# NixieSocket.net
KiCad netlist of a schematic drawn in Altium Designer
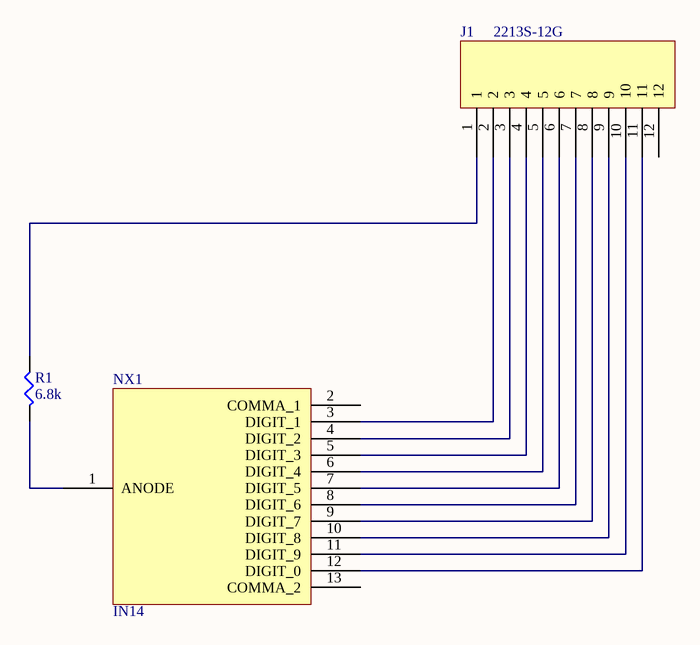
[diagram p0: NixieSocket.SchDoc]

(export (version "E")
  (design (tool "Eeschema 10.0.6"))
  (components
    (comp (ref "J1")
      (value "2213S-12G")
      (footprint "Header 2.54mm 6x2 - Male")
      (libsource (lib "Connectors") (part "2213S-12G"))
    )
    (comp (ref "NX1")
      (value "IN14")
      (footprint "IN-14 Nixie Tube")
      (description "IN-14 Nixie Tube")
      (libsource (lib "IN14") (part "IN14"))
    )
    (comp (ref "R1")
      (value "6.8k")
      (footprint "SMD-0805-RES")
      (description "RES SMD 6.8K OHM 1% 1/2W 0805")
      (fields
        (field (name "PART NUMBER") "ERJ-P6WF6801V")
        (field (name "DIGI-KEY PART NUMBER") "P16895CT-ND")
      )
      (libsource (lib "Panasonic_ERJ_0805") (part "ERJ-P6WF6801V"))
    )
  )
  (nets
    (net (code "1") (name "Net-(J1-Pad1)") (class "Default")
      (node (ref "J1") (pin "1") (pinfunction "1_1") (pintype "passive"))
      (node (ref "R1") (pin "1") (pinfunction "1_1") (pintype "passive"))
    )
    (net (code "2") (name "Net-(NX1-ANODE)") (class "Default")
      (node (ref "NX1") (pin "1") (pinfunction "ANODE_1") (pintype "passive"))
      (node (ref "R1") (pin "2") (pinfunction "2_2") (pintype "passive"))
    )
    (net (code "3") (name "Net-(NX1-DIGIT_0)") (class "Default")
      (node (ref "J1") (pin "11") (pinfunction "11_11") (pintype "passive"))
      (node (ref "NX1") (pin "12") (pinfunction "DIGIT_0_12") (pintype "passive"))
    )
    (net (code "4") (name "Net-(NX1-DIGIT_1)") (class "Default")
      (node (ref "J1") (pin "2") (pinfunction "2_2") (pintype "passive"))
      (node (ref "NX1") (pin "3") (pinfunction "DIGIT_1_3") (pintype "passive"))
    )
    (net (code "5") (name "Net-(NX1-DIGIT_2)") (class "Default")
      (node (ref "J1") (pin "3") (pinfunction "3_3") (pintype "passive"))
      (node (ref "NX1") (pin "4") (pinfunction "DIGIT_2_4") (pintype "passive"))
    )
    (net (code "6") (name "Net-(NX1-DIGIT_3)") (class "Default")
      (node (ref "J1") (pin "4") (pinfunction "4_4") (pintype "passive"))
      (node (ref "NX1") (pin "5") (pinfunction "DIGIT_3_5") (pintype "passive"))
    )
    (net (code "7") (name "Net-(NX1-DIGIT_4)") (class "Default")
      (node (ref "J1") (pin "5") (pinfunction "5_5") (pintype "passive"))
      (node (ref "NX1") (pin "6") (pinfunction "DIGIT_4_6") (pintype "passive"))
    )
    (net (code "8") (name "Net-(NX1-DIGIT_5)") (class "Default")
      (node (ref "J1") (pin "6") (pinfunction "6_6") (pintype "passive"))
      (node (ref "NX1") (pin "7") (pinfunction "DIGIT_5_7") (pintype "passive"))
    )
    (net (code "9") (name "Net-(NX1-DIGIT_6)") (class "Default")
      (node (ref "J1") (pin "7") (pinfunction "7_7") (pintype "passive"))
      (node (ref "NX1") (pin "8") (pinfunction "DIGIT_6_8") (pintype "passive"))
    )
    (net (code "10") (name "Net-(NX1-DIGIT_7)") (class "Default")
      (node (ref "J1") (pin "8") (pinfunction "8_8") (pintype "passive"))
      (node (ref "NX1") (pin "9") (pinfunction "DIGIT_7_9") (pintype "passive"))
    )
    (net (code "11") (name "Net-(NX1-DIGIT_8)") (class "Default")
      (node (ref "J1") (pin "9") (pinfunction "9_9") (pintype "passive"))
      (node (ref "NX1") (pin "10") (pinfunction "DIGIT_8_10") (pintype "passive"))
    )
    (net (code "12") (name "Net-(NX1-DIGIT_9)") (class "Default")
      (node (ref "J1") (pin "10") (pinfunction "10_10") (pintype "passive"))
      (node (ref "NX1") (pin "11") (pinfunction "DIGIT_9_11") (pintype "passive"))
    )
    (net (code "13") (name "unconnected-(J1-Pad12)") (class "Default")
      (node (ref "J1") (pin "12") (pinfunction "12_12") (pintype "passive"))
    )
    (net (code "14") (name "unconnected-(NX1-COMMA_1-Pad2)") (class "Default")
      (node (ref "NX1") (pin "2") (pinfunction "COMMA_1_2") (pintype "passive"))
    )
    (net (code "15") (name "unconnected-(NX1-COMMA_2-Pad13)") (class "Default")
      (node (ref "NX1") (pin "13") (pinfunction "COMMA_2_13") (pintype "passive"))
    )
  )
)
